# pcb.net
KiCad netlist of a schematic drawn in EAGLE
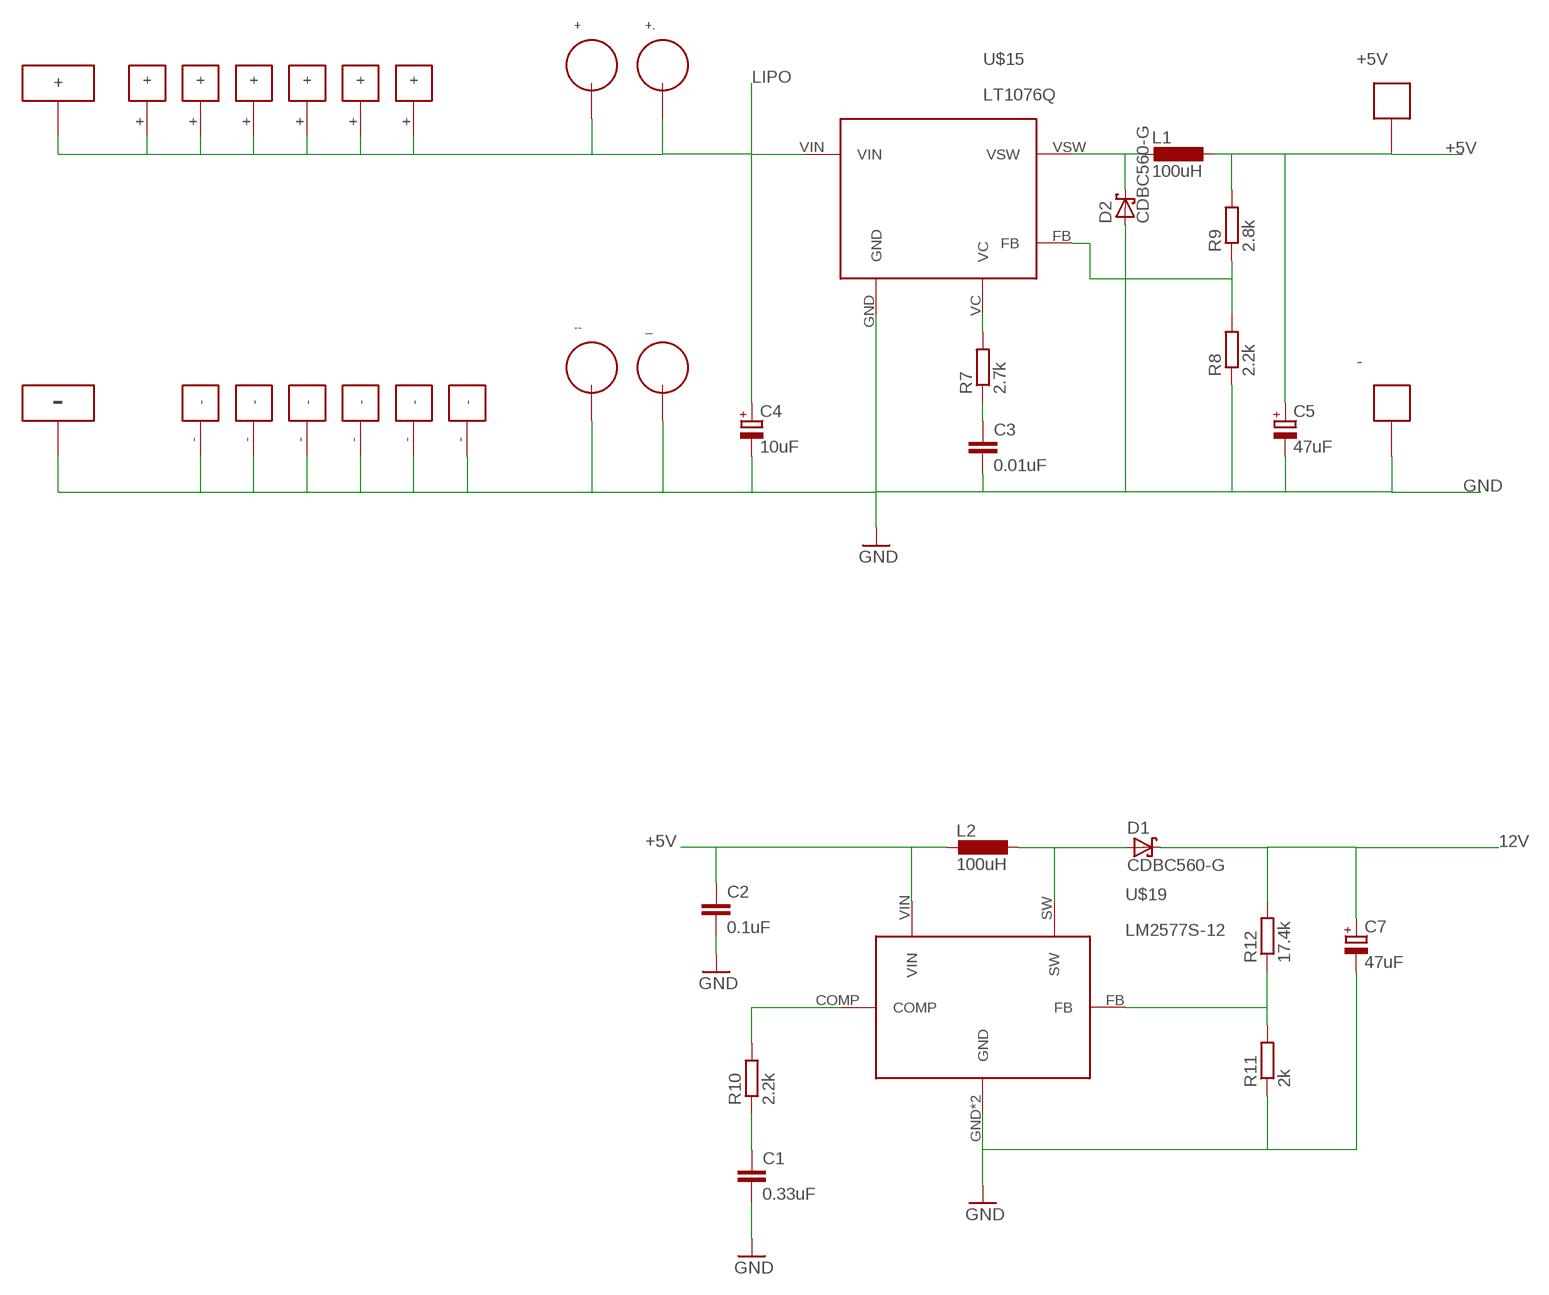
[diagram p0: schematic, sheet 1, part 1 of 2]
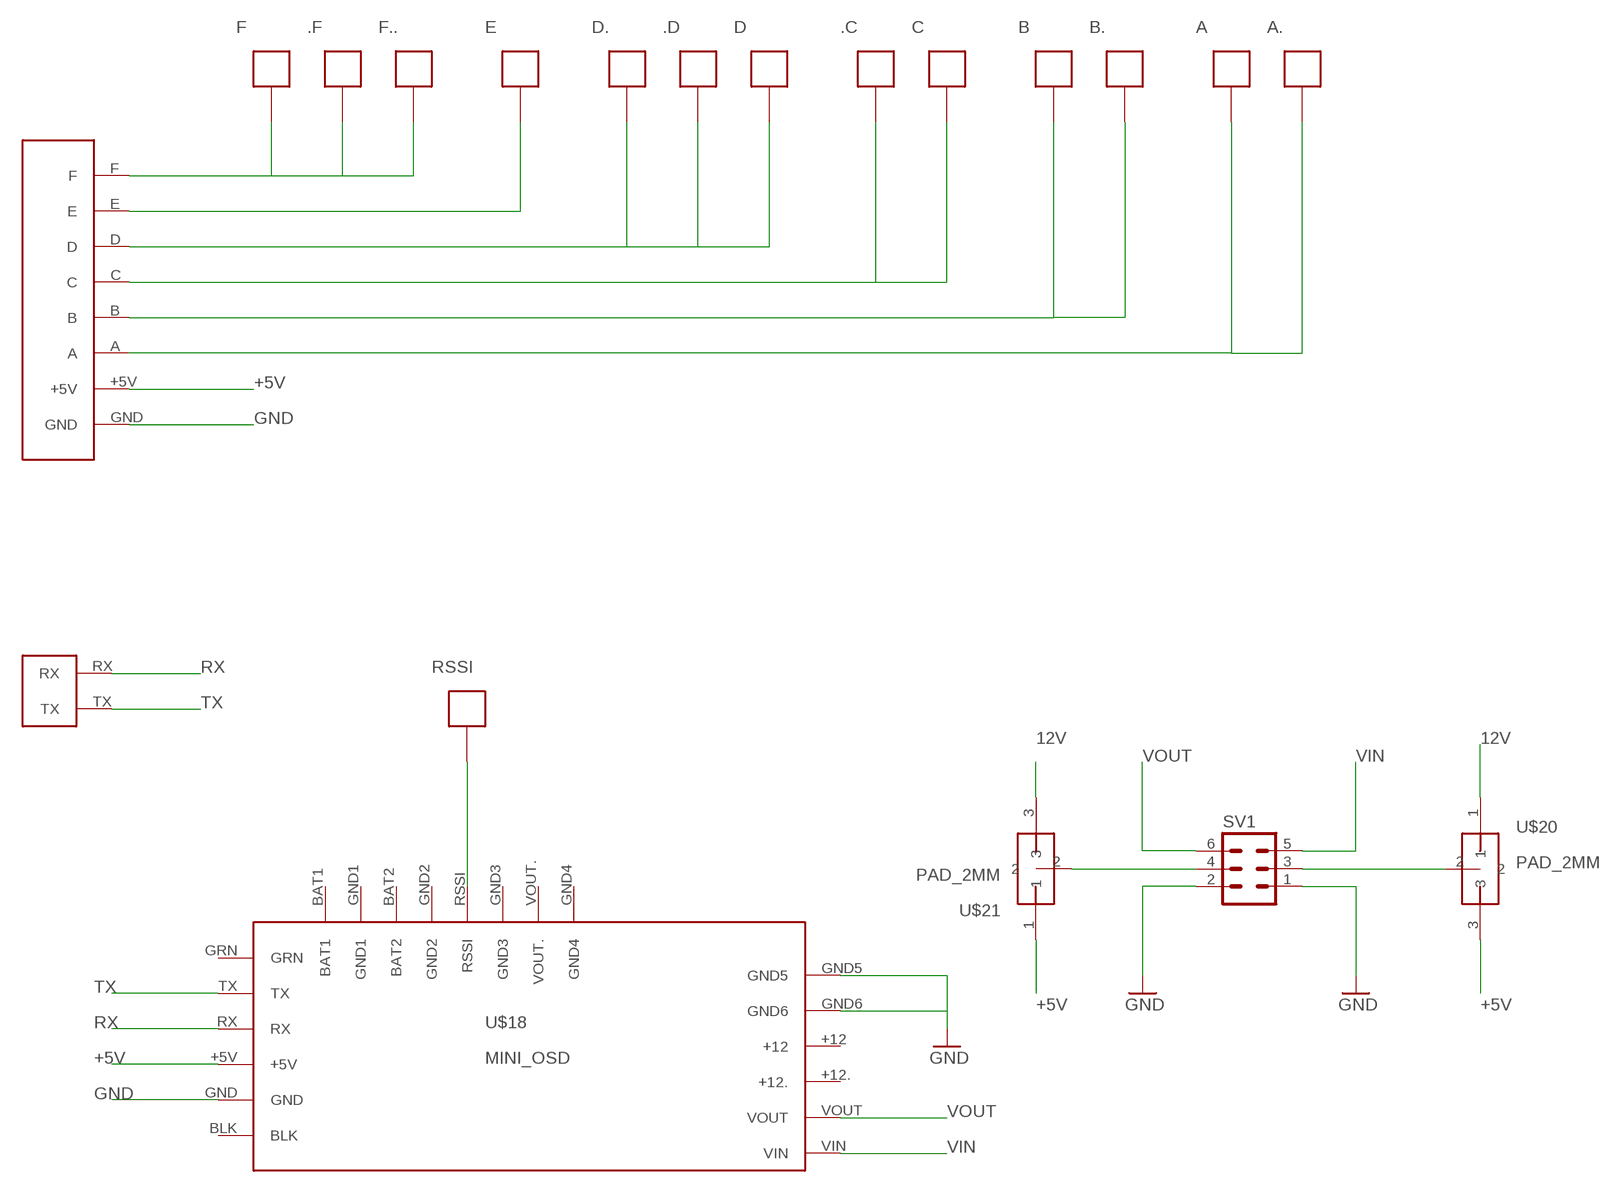
[diagram p1: schematic, sheet 1, part 2 of 2]

(export (version "E")
  (design (tool "Eeschema 10.0.6"))
  (components
    (comp (ref "+")
      (value "PAD_POWER")
      (footprint "eagle-import:PAD_POWER")
      (libsource (lib "eagle-import") (part "PAD_POWER"))
    )
    (comp (ref "+.")
      (value "PAD_POWER")
      (footprint "eagle-import:PAD_POWER")
      (libsource (lib "eagle-import") (part "PAD_POWER"))
    )
    (comp (ref "+5V")
      (value "PAD3-A")
      (footprint "eagle-import:PAD3-A")
      (libsource (lib "eagle-import") (part "PAD3-A"))
    )
    (comp (ref "-")
      (value "PAD3-A")
      (footprint "eagle-import:PAD3-A")
      (libsource (lib "eagle-import") (part "PAD3-A"))
    )
    (comp (ref "--")
      (value "PAD_POWER")
      (footprint "eagle-import:PAD_POWER")
      (libsource (lib "eagle-import") (part "PAD_POWER"))
    )
    (comp (ref ".C")
      (value "PAD3-A")
      (footprint "eagle-import:PAD3-A")
      (libsource (lib "eagle-import") (part "PAD3-A"))
    )
    (comp (ref ".D")
      (value "PAD3-A")
      (footprint "eagle-import:PAD3-A")
      (libsource (lib "eagle-import") (part "PAD3-A"))
    )
    (comp (ref ".F")
      (value "PAD3-A")
      (footprint "eagle-import:PAD3-A")
      (libsource (lib "eagle-import") (part "PAD3-A"))
    )
    (comp (ref "A")
      (value "PAD3-A")
      (footprint "eagle-import:PAD3-A")
      (libsource (lib "eagle-import") (part "PAD3-A"))
    )
    (comp (ref "A.")
      (value "PAD3-A")
      (footprint "eagle-import:PAD3-A")
      (libsource (lib "eagle-import") (part "PAD3-A"))
    )
    (comp (ref "B")
      (value "PAD3-A")
      (footprint "eagle-import:PAD3-A")
      (libsource (lib "eagle-import") (part "PAD3-A"))
    )
    (comp (ref "B.")
      (value "PAD3-A")
      (footprint "eagle-import:PAD3-A")
      (libsource (lib "eagle-import") (part "PAD3-A"))
    )
    (comp (ref "C")
      (value "PAD3-A")
      (footprint "eagle-import:PAD3-A")
      (libsource (lib "eagle-import") (part "PAD3-A"))
    )
    (comp (ref "C1")
      (value "0.33uF")
      (footprint "eagle-import:C1206")
      (libsource (lib "eagle-import") (part "C-EUC1206"))
    )
    (comp (ref "C2")
      (value "0.1uF")
      (footprint "eagle-import:C1206")
      (libsource (lib "eagle-import") (part "C-EUC1206"))
    )
    (comp (ref "C3")
      (value "0.01uF")
      (footprint "eagle-import:C1206")
      (libsource (lib "eagle-import") (part "C-EUC1206"))
    )
    (comp (ref "C4")
      (value "10uF")
      (footprint "eagle-import:153CLV-0505")
      (libsource (lib "eagle-import") (part "CPOL-EU153CLV-0505"))
    )
    (comp (ref "C5")
      (value "47uF")
      (footprint "eagle-import:153CLV-0505")
      (libsource (lib "eagle-import") (part "CPOL-EU153CLV-0505"))
    )
    (comp (ref "C7")
      (value "47uF")
      (footprint "eagle-import:153CLV-0505")
      (libsource (lib "eagle-import") (part "CPOL-EU153CLV-0505"))
    )
    (comp (ref "D")
      (value "PAD3-A")
      (footprint "eagle-import:PAD3-A")
      (libsource (lib "eagle-import") (part "PAD3-A"))
    )
    (comp (ref "D.")
      (value "PAD3-A")
      (footprint "eagle-import:PAD3-A")
      (libsource (lib "eagle-import") (part "PAD3-A"))
    )
    (comp (ref "D1")
      (value "CDBC560-G")
      (footprint "eagle-import:SMC")
      (libsource (lib "eagle-import") (part "MBRS30T32"))
    )
    (comp (ref "D2")
      (value "CDBC560-G")
      (footprint "eagle-import:SMC")
      (libsource (lib "eagle-import") (part "MBRS30T32"))
    )
    (comp (ref "E")
      (value "PAD3-A")
      (footprint "eagle-import:PAD3-A")
      (libsource (lib "eagle-import") (part "PAD3-A"))
    )
    (comp (ref "F")
      (value "PAD3-A")
      (footprint "eagle-import:PAD3-A")
      (libsource (lib "eagle-import") (part "PAD3-A"))
    )
    (comp (ref "F..")
      (value "PAD3-A")
      (footprint "eagle-import:PAD3-A")
      (libsource (lib "eagle-import") (part "PAD3-A"))
    )
    (comp (ref "L1")
      (value "100uH")
      (footprint "eagle-import:DO3316P")
      (libsource (lib "eagle-import") (part "DO3316P"))
    )
    (comp (ref "L2")
      (value "100uH")
      (footprint "eagle-import:DO3316P")
      (fields (field (name "OC_FARNELL") "unknown") (field (name "OC_NEWARK") "unknown"))
      (libsource (lib "eagle-import") (part "DO3316P"))
    )
    (comp (ref "R7")
      (value "2.7k")
      (footprint "eagle-import:R0805")
      (libsource (lib "eagle-import") (part "R-EU_R0805"))
    )
    (comp (ref "R8")
      (value "2.2k")
      (footprint "eagle-import:R0805")
      (libsource (lib "eagle-import") (part "R-EU_R0805"))
    )
    (comp (ref "R9")
      (value "2.8k")
      (footprint "eagle-import:R0805")
      (libsource (lib "eagle-import") (part "R-EU_R0805"))
    )
    (comp (ref "R10")
      (value "2.2k")
      (footprint "eagle-import:R0805")
      (libsource (lib "eagle-import") (part "R-EU_R0805"))
    )
    (comp (ref "R11")
      (value "2k")
      (footprint "eagle-import:R0805")
      (libsource (lib "eagle-import") (part "R-EU_R0805"))
    )
    (comp (ref "R12")
      (value "17.4k")
      (footprint "eagle-import:R0805")
      (libsource (lib "eagle-import") (part "R-EU_R0805"))
    )
    (comp (ref "RSSI")
      (value "PAD3-A")
      (footprint "eagle-import:PAD3-A")
      (libsource (lib "eagle-import") (part "PAD3-A"))
    )
    (comp (ref "SV1")
      (value "MA03-2")
      (footprint "eagle-import:MA03-2")
      (libsource (lib "eagle-import") (part "MA03-2"))
    )
    (comp (ref "U$1")
      (value "PAD6X3.5-")
      (footprint "eagle-import:PAD6X3.5")
      (libsource (lib "eagle-import") (part "PAD6X3.5-"))
    )
    (comp (ref "U$2")
      (value "PAD6X3.5+")
      (footprint "eagle-import:PAD6X3.5")
      (libsource (lib "eagle-import") (part "PAD6X3.5+"))
    )
    (comp (ref "U$3")
      (value "PAD3.81+")
      (footprint "eagle-import:PAD3.81")
      (libsource (lib "eagle-import") (part "PAD3.81+"))
    )
    (comp (ref "U$4")
      (value "PAD3.81+")
      (footprint "eagle-import:PAD3.81")
      (libsource (lib "eagle-import") (part "PAD3.81+"))
    )
    (comp (ref "U$5")
      (value "PAD3.81-")
      (footprint "eagle-import:PAD3.81-")
      (libsource (lib "eagle-import") (part "PAD3.81-"))
    )
    (comp (ref "U$7")
      (value "PAD3.81+")
      (footprint "eagle-import:PAD3.81")
      (libsource (lib "eagle-import") (part "PAD3.81+"))
    )
    (comp (ref "U$8")
      (value "PAD3.81+")
      (footprint "eagle-import:PAD3.81")
      (libsource (lib "eagle-import") (part "PAD3.81+"))
    )
    (comp (ref "U$9")
      (value "PAD3.81-")
      (footprint "eagle-import:PAD3.81-")
      (libsource (lib "eagle-import") (part "PAD3.81-"))
    )
    (comp (ref "U$10")
      (value "PAD3.81-")
      (footprint "eagle-import:PAD3.81-")
      (libsource (lib "eagle-import") (part "PAD3.81-"))
    )
    (comp (ref "U$11")
      (value "PAD3.81-")
      (footprint "eagle-import:PAD3.81-")
      (libsource (lib "eagle-import") (part "PAD3.81-"))
    )
    (comp (ref "U$12")
      (value "PAD3.81-")
      (footprint "eagle-import:PAD3.81-")
      (libsource (lib "eagle-import") (part "PAD3.81-"))
    )
    (comp (ref "U$13")
      (value "PAD3.81+")
      (footprint "eagle-import:PAD3.81")
      (libsource (lib "eagle-import") (part "PAD3.81+"))
    )
    (comp (ref "U$14")
      (value "PAD3.81+")
      (footprint "eagle-import:PAD3.81")
      (libsource (lib "eagle-import") (part "PAD3.81+"))
    )
    (comp (ref "U$15")
      (value "LT1076Q")
      (footprint "eagle-import:LT1076")
      (libsource (lib "eagle-import") (part "LT1076Q"))
    )
    (comp (ref "U$16")
      (value "2.54HEADER8")
      (footprint "eagle-import:2.54HEADER8")
      (libsource (lib "eagle-import") (part "2.54HEADER8"))
    )
    (comp (ref "U$17")
      (value "2.54HEADER")
      (footprint "eagle-import:2.54HEADER")
      (libsource (lib "eagle-import") (part "2.54HEADER"))
    )
    (comp (ref "U$18")
      (value "MINI_OSD")
      (footprint "eagle-import:MINI_OSD")
      (libsource (lib "eagle-import") (part "MINI_OSD"))
    )
    (comp (ref "U$19")
      (value "LM2577S-12")
      (footprint "eagle-import:TO-263")
      (libsource (lib "eagle-import") (part "LM2577S-12"))
    )
    (comp (ref "U$20")
      (value "PAD_2MM")
      (footprint "eagle-import:PAD_2MM")
      (libsource (lib "eagle-import") (part "PAD_2MM"))
    )
    (comp (ref "U$21")
      (value "PAD_2MM")
      (footprint "eagle-import:PAD_2MM")
      (libsource (lib "eagle-import") (part "PAD_2MM"))
    )
    (comp (ref "U$22")
      (value "PAD3.81-")
      (footprint "eagle-import:PAD3.81-")
      (libsource (lib "eagle-import") (part "PAD3.81-"))
    )
    (comp (ref "_")
      (value "PAD_POWER")
      (footprint "eagle-import:PAD_POWER")
      (libsource (lib "eagle-import") (part "PAD_POWER"))
    )
  )
  (nets
    (net (code "1") (name "/+5V") (class "Default")
      (node (ref "+5V") (pin "1") (pinfunction "1_1") (pintype "bidirectional"))
      (node (ref "C2") (pin "1") (pinfunction "1_1") (pintype "passive"))
      (node (ref "C5") (pin "+") (pinfunction "+_+") (pintype "passive"))
      (node (ref "L1") (pin "2") (pinfunction "2_2") (pintype "passive"))
      (node (ref "L2") (pin "1") (pinfunction "1_1") (pintype "passive"))
      (node (ref "R9") (pin "2") (pinfunction "2_2") (pintype "passive"))
      (node (ref "U$16") (pin "+5V") (pinfunction "+5V_+5V") (pintype "bidirectional"))
      (node (ref "U$18") (pin "+5V") (pinfunction "+5V_+5V") (pintype "bidirectional"))
      (node (ref "U$19") (pin "VIN") (pinfunction "VIN_VIN") (pintype "bidirectional"))
      (node (ref "U$20") (pin "3") (pinfunction "3_3") (pintype "bidirectional"))
      (node (ref "U$21") (pin "1") (pinfunction "1_1") (pintype "bidirectional"))
    )
    (net (code "2") (name "/12V") (class "Default")
      (node (ref "C7") (pin "+") (pinfunction "+_+") (pintype "passive"))
      (node (ref "D1") (pin "C") (pinfunction "C_C") (pintype "passive"))
      (node (ref "R12") (pin "2") (pinfunction "2_2") (pintype "passive"))
      (node (ref "U$20") (pin "1") (pinfunction "1_1") (pintype "bidirectional"))
      (node (ref "U$21") (pin "3") (pinfunction "3_3") (pintype "bidirectional"))
    )
    (net (code "3") (name "/LIPO") (class "Default")
      (node (ref "+") (pin "P$1") (pinfunction "P$1_P$1") (pintype "bidirectional"))
      (node (ref "+") (pin "P$2") (pinfunction "P$1_P$2") (pintype "bidirectional"))
      (node (ref "+") (pin "P$3") (pinfunction "P$1_P$3") (pintype "bidirectional"))
      (node (ref "+") (pin "P$4") (pinfunction "P$1_P$4") (pintype "bidirectional"))
      (node (ref "+") (pin "P$5") (pinfunction "P$1_P$5") (pintype "bidirectional"))
      (node (ref "+") (pin "P$6") (pinfunction "P$1_P$6") (pintype "bidirectional"))
      (node (ref "+") (pin "P$7") (pinfunction "P$1_P$7") (pintype "bidirectional"))
      (node (ref "+") (pin "P$8") (pinfunction "P$1_P$8") (pintype "bidirectional"))
      (node (ref "+") (pin "P$9") (pinfunction "P$1_P$9") (pintype "bidirectional"))
      (node (ref "+.") (pin "P$1") (pinfunction "P$1_P$1") (pintype "bidirectional"))
      (node (ref "+.") (pin "P$2") (pinfunction "P$1_P$2") (pintype "bidirectional"))
      (node (ref "+.") (pin "P$3") (pinfunction "P$1_P$3") (pintype "bidirectional"))
      (node (ref "+.") (pin "P$4") (pinfunction "P$1_P$4") (pintype "bidirectional"))
      (node (ref "+.") (pin "P$5") (pinfunction "P$1_P$5") (pintype "bidirectional"))
      (node (ref "+.") (pin "P$6") (pinfunction "P$1_P$6") (pintype "bidirectional"))
      (node (ref "+.") (pin "P$7") (pinfunction "P$1_P$7") (pintype "bidirectional"))
      (node (ref "+.") (pin "P$8") (pinfunction "P$1_P$8") (pintype "bidirectional"))
      (node (ref "+.") (pin "P$9") (pinfunction "P$1_P$9") (pintype "bidirectional"))
      (node (ref "C4") (pin "+") (pinfunction "+_+") (pintype "passive"))
      (node (ref "U$13") (pin "+") (pinfunction "+_+") (pintype "bidirectional"))
      (node (ref "U$14") (pin "+") (pinfunction "+_+") (pintype "bidirectional"))
      (node (ref "U$15") (pin "VIN") (pinfunction "VIN_VIN") (pintype "bidirectional"))
      (node (ref "U$2") (pin "P$1") (pinfunction "+_P$1") (pintype "bidirectional"))
      (node (ref "U$3") (pin "+") (pinfunction "+_+") (pintype "bidirectional"))
      (node (ref "U$4") (pin "+") (pinfunction "+_+") (pintype "bidirectional"))
      (node (ref "U$7") (pin "+") (pinfunction "+_+") (pintype "bidirectional"))
      (node (ref "U$8") (pin "+") (pinfunction "+_+") (pintype "bidirectional"))
    )
    (net (code "4") (name "/RX") (class "Default")
      (node (ref "U$17") (pin "RX") (pinfunction "RX_RX") (pintype "bidirectional"))
      (node (ref "U$18") (pin "RX") (pinfunction "RX_RX") (pintype "bidirectional"))
    )
    (net (code "5") (name "/TX") (class "Default")
      (node (ref "U$17") (pin "TX") (pinfunction "TX_TX") (pintype "bidirectional"))
      (node (ref "U$18") (pin "TX") (pinfunction "TX_TX") (pintype "bidirectional"))
    )
    (net (code "6") (name "/VIN") (class "Default")
      (node (ref "SV1") (pin "5") (pinfunction "5_5") (pintype "passive"))
      (node (ref "U$18") (pin "VIN") (pinfunction "VIN_VIN") (pintype "bidirectional"))
    )
    (net (code "7") (name "/VOUT") (class "Default")
      (node (ref "SV1") (pin "6") (pinfunction "6_6") (pintype "passive"))
      (node (ref "U$18") (pin "VOUT") (pinfunction "VOUT_VOUT") (pintype "bidirectional"))
    )
    (net (code "8") (name "GND") (class "Default")
      (node (ref "-") (pin "1") (pinfunction "1_1") (pintype "bidirectional"))
      (node (ref "--") (pin "P$1") (pinfunction "P$1_P$1") (pintype "bidirectional"))
      (node (ref "--") (pin "P$2") (pinfunction "P$1_P$2") (pintype "bidirectional"))
      (node (ref "--") (pin "P$3") (pinfunction "P$1_P$3") (pintype "bidirectional"))
      (node (ref "--") (pin "P$4") (pinfunction "P$1_P$4") (pintype "bidirectional"))
      (node (ref "--") (pin "P$5") (pinfunction "P$1_P$5") (pintype "bidirectional"))
      (node (ref "--") (pin "P$6") (pinfunction "P$1_P$6") (pintype "bidirectional"))
      (node (ref "--") (pin "P$7") (pinfunction "P$1_P$7") (pintype "bidirectional"))
      (node (ref "--") (pin "P$8") (pinfunction "P$1_P$8") (pintype "bidirectional"))
      (node (ref "--") (pin "P$9") (pinfunction "P$1_P$9") (pintype "bidirectional"))
      (node (ref "C1") (pin "2") (pinfunction "2_2") (pintype "passive"))
      (node (ref "C2") (pin "2") (pinfunction "2_2") (pintype "passive"))
      (node (ref "C3") (pin "2") (pinfunction "2_2") (pintype "passive"))
      (node (ref "C4") (pin "-") (pinfunction "-_-") (pintype "passive"))
      (node (ref "C5") (pin "-") (pinfunction "-_-") (pintype "passive"))
      (node (ref "C7") (pin "-") (pinfunction "-_-") (pintype "passive"))
      (node (ref "D2") (pin "A") (pinfunction "A_A") (pintype "passive"))
      (node (ref "R11") (pin "1") (pinfunction "1_1") (pintype "passive"))
      (node (ref "R8") (pin "1") (pinfunction "1_1") (pintype "passive"))
      (node (ref "SV1") (pin "1") (pinfunction "1_1") (pintype "passive"))
      (node (ref "SV1") (pin "2") (pinfunction "2_2") (pintype "passive"))
      (node (ref "U$1") (pin "P$1") (pinfunction "P$1_P$1") (pintype "bidirectional"))
      (node (ref "U$10") (pin "-") (pinfunction "-_-") (pintype "bidirectional"))
      (node (ref "U$11") (pin "-") (pinfunction "-_-") (pintype "bidirectional"))
      (node (ref "U$12") (pin "-") (pinfunction "-_-") (pintype "bidirectional"))
      (node (ref "U$15") (pin "GND") (pinfunction "GND_GND") (pintype "bidirectional"))
      (node (ref "U$16") (pin "GND") (pinfunction "GND_GND") (pintype "bidirectional"))
      (node (ref "U$18") (pin "GND") (pinfunction "GND_GND") (pintype "bidirectional"))
      (node (ref "U$18") (pin "GND5") (pinfunction "GND5_GND5") (pintype "bidirectional"))
      (node (ref "U$18") (pin "GND6") (pinfunction "GND6_GND6") (pintype "bidirectional"))
      (node (ref "U$19") (pin "GND") (pinfunction "GND_GND") (pintype "bidirectional"))
      (node (ref "U$19") (pin "GND1") (pinfunction "GND_GND1") (pintype "bidirectional"))
      (node (ref "U$22") (pin "-") (pinfunction "-_-") (pintype "bidirectional"))
      (node (ref "U$5") (pin "-") (pinfunction "-_-") (pintype "bidirectional"))
      (node (ref "U$9") (pin "-") (pinfunction "-_-") (pintype "bidirectional"))
      (node (ref "_") (pin "P$1") (pinfunction "P$1_P$1") (pintype "bidirectional"))
      (node (ref "_") (pin "P$2") (pinfunction "P$1_P$2") (pintype "bidirectional"))
      (node (ref "_") (pin "P$3") (pinfunction "P$1_P$3") (pintype "bidirectional"))
      (node (ref "_") (pin "P$4") (pinfunction "P$1_P$4") (pintype "bidirectional"))
      (node (ref "_") (pin "P$5") (pinfunction "P$1_P$5") (pintype "bidirectional"))
      (node (ref "_") (pin "P$6") (pinfunction "P$1_P$6") (pintype "bidirectional"))
      (node (ref "_") (pin "P$7") (pinfunction "P$1_P$7") (pintype "bidirectional"))
      (node (ref "_") (pin "P$8") (pinfunction "P$1_P$8") (pintype "bidirectional"))
      (node (ref "_") (pin "P$9") (pinfunction "P$1_P$9") (pintype "bidirectional"))
    )
    (net (code "9") (name "Net-(.C-Pad1)") (class "Default")
      (node (ref ".C") (pin "1") (pinfunction "1_1") (pintype "bidirectional"))
      (node (ref "C") (pin "1") (pinfunction "1_1") (pintype "bidirectional"))
      (node (ref "U$16") (pin "C") (pinfunction "C_C") (pintype "bidirectional"))
    )
    (net (code "10") (name "Net-(.D-Pad1)") (class "Default")
      (node (ref ".D") (pin "1") (pinfunction "1_1") (pintype "bidirectional"))
      (node (ref "D") (pin "1") (pinfunction "1_1") (pintype "bidirectional"))
      (node (ref "D.") (pin "1") (pinfunction "1_1") (pintype "bidirectional"))
      (node (ref "U$16") (pin "D") (pinfunction "D_D") (pintype "bidirectional"))
    )
    (net (code "11") (name "Net-(.F-Pad1)") (class "Default")
      (node (ref ".F") (pin "1") (pinfunction "1_1") (pintype "bidirectional"))
      (node (ref "F") (pin "1") (pinfunction "1_1") (pintype "bidirectional"))
      (node (ref "F..") (pin "1") (pinfunction "1_1") (pintype "bidirectional"))
      (node (ref "U$16") (pin "F") (pinfunction "F_F") (pintype "bidirectional"))
    )
    (net (code "12") (name "Net-(A-Pad1)") (class "Default")
      (node (ref "A") (pin "1") (pinfunction "1_1") (pintype "bidirectional"))
      (node (ref "A.") (pin "1") (pinfunction "1_1") (pintype "bidirectional"))
      (node (ref "U$16") (pin "A") (pinfunction "A_A") (pintype "bidirectional"))
    )
    (net (code "13") (name "Net-(B-Pad1)") (class "Default")
      (node (ref "B") (pin "1") (pinfunction "1_1") (pintype "bidirectional"))
      (node (ref "B.") (pin "1") (pinfunction "1_1") (pintype "bidirectional"))
      (node (ref "U$16") (pin "B") (pinfunction "B_B") (pintype "bidirectional"))
    )
    (net (code "14") (name "Net-(C1-Pad1)") (class "Default")
      (node (ref "C1") (pin "1") (pinfunction "1_1") (pintype "passive"))
      (node (ref "R10") (pin "1") (pinfunction "1_1") (pintype "passive"))
    )
    (net (code "15") (name "Net-(C3-Pad1)") (class "Default")
      (node (ref "C3") (pin "1") (pinfunction "1_1") (pintype "passive"))
      (node (ref "R7") (pin "1") (pinfunction "1_1") (pintype "passive"))
    )
    (net (code "16") (name "Net-(D1-PadA)") (class "Default")
      (node (ref "D1") (pin "A") (pinfunction "A_A") (pintype "passive"))
      (node (ref "L2") (pin "2") (pinfunction "2_2") (pintype "passive"))
      (node (ref "U$19") (pin "SW") (pinfunction "SW_SW") (pintype "bidirectional"))
    )
    (net (code "17") (name "Net-(D2-PadC)") (class "Default")
      (node (ref "D2") (pin "C") (pinfunction "C_C") (pintype "passive"))
      (node (ref "L1") (pin "1") (pinfunction "1_1") (pintype "passive"))
      (node (ref "U$15") (pin "VSW") (pinfunction "VSW_VSW") (pintype "bidirectional"))
    )
    (net (code "18") (name "Net-(E-Pad1)") (class "Default")
      (node (ref "E") (pin "1") (pinfunction "1_1") (pintype "bidirectional"))
      (node (ref "U$16") (pin "E") (pinfunction "E_E") (pintype "bidirectional"))
    )
    (net (code "19") (name "Net-(R7-Pad2)") (class "Default")
      (node (ref "R7") (pin "2") (pinfunction "2_2") (pintype "passive"))
      (node (ref "U$15") (pin "VC") (pinfunction "VC_VC") (pintype "bidirectional"))
    )
    (net (code "20") (name "Net-(R8-Pad2)") (class "Default")
      (node (ref "R8") (pin "2") (pinfunction "2_2") (pintype "passive"))
      (node (ref "R9") (pin "1") (pinfunction "1_1") (pintype "passive"))
      (node (ref "U$15") (pin "FB") (pinfunction "FB_FB") (pintype "bidirectional"))
    )
    (net (code "21") (name "Net-(R10-Pad2)") (class "Default")
      (node (ref "R10") (pin "2") (pinfunction "2_2") (pintype "passive"))
      (node (ref "U$19") (pin "COMP") (pinfunction "COMP_COMP") (pintype "bidirectional"))
    )
    (net (code "22") (name "Net-(R11-Pad2)") (class "Default")
      (node (ref "R11") (pin "2") (pinfunction "2_2") (pintype "passive"))
      (node (ref "R12") (pin "1") (pinfunction "1_1") (pintype "passive"))
      (node (ref "U$19") (pin "FB") (pinfunction "FB_FB") (pintype "bidirectional"))
    )
    (net (code "23") (name "Net-(RSSI-Pad1)") (class "Default")
      (node (ref "RSSI") (pin "1") (pinfunction "1_1") (pintype "bidirectional"))
      (node (ref "U$18") (pin "RSSI") (pinfunction "RSSI_RSSI") (pintype "bidirectional"))
    )
    (net (code "24") (name "Net-(SV1-Pad3)") (class "Default")
      (node (ref "SV1") (pin "3") (pinfunction "3_3") (pintype "passive"))
      (node (ref "U$20") (pin "2") (pinfunction "2_2") (pintype "bidirectional"))
    )
    (net (code "25") (name "Net-(SV1-Pad4)") (class "Default")
      (node (ref "SV1") (pin "4") (pinfunction "4_4") (pintype "passive"))
      (node (ref "U$21") (pin "2") (pinfunction "2_2") (pintype "bidirectional"))
    )
    (net (code "26") (name "unconnected-(U$18-Pad+12)") (class "Default")
      (node (ref "U$18") (pin "+12") (pinfunction "+12_+12") (pintype "bidirectional"))
    )
    (net (code "27") (name "unconnected-(U$18-Pad+12.)") (class "Default")
      (node (ref "U$18") (pin "+12.") (pinfunction "+12._+12.") (pintype "bidirectional"))
    )
    (net (code "28") (name "unconnected-(U$18-PadBAT1)") (class "Default")
      (node (ref "U$18") (pin "BAT1") (pinfunction "BAT1_BAT1") (pintype "bidirectional"))
    )
    (net (code "29") (name "unconnected-(U$18-PadBAT2)") (class "Default")
      (node (ref "U$18") (pin "BAT2") (pinfunction "BAT2_BAT2") (pintype "bidirectional"))
    )
    (net (code "30") (name "unconnected-(U$18-PadBLK)") (class "Default")
      (node (ref "U$18") (pin "BLK") (pinfunction "BLK_BLK") (pintype "bidirectional"))
    )
    (net (code "31") (name "unconnected-(U$18-PadGND1)") (class "Default")
      (node (ref "U$18") (pin "GND1") (pinfunction "GND1_GND1") (pintype "bidirectional"))
    )
    (net (code "32") (name "unconnected-(U$18-PadGND2)") (class "Default")
      (node (ref "U$18") (pin "GND2") (pinfunction "GND2_GND2") (pintype "bidirectional"))
    )
    (net (code "33") (name "unconnected-(U$18-PadGND3)") (class "Default")
      (node (ref "U$18") (pin "GND3") (pinfunction "GND3_GND3") (pintype "bidirectional"))
    )
    (net (code "34") (name "unconnected-(U$18-PadGND4)") (class "Default")
      (node (ref "U$18") (pin "GND4") (pinfunction "GND4_GND4") (pintype "bidirectional"))
    )
    (net (code "35") (name "unconnected-(U$18-PadGRN)") (class "Default")
      (node (ref "U$18") (pin "GRN") (pinfunction "GRN_GRN") (pintype "bidirectional"))
    )
    (net (code "36") (name "unconnected-(U$18-PadVOUT.)") (class "Default")
      (node (ref "U$18") (pin "VOUT.") (pinfunction "VOUT._VOUT.") (pintype "bidirectional"))
    )
  )
)
